# Charger.net
KiCad netlist of a schematic drawn in EAGLE
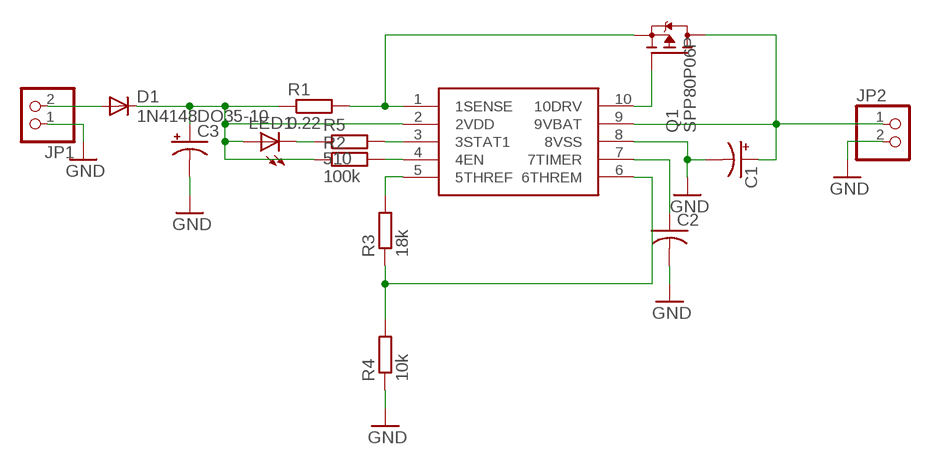
[diagram p0: schematic, sheet 1]

(export (version "E")
  (design (tool "Eeschema 10.0.6"))
  (components
    (comp (ref "C1")
      (value "CPOL-US153CLV-0505")
      (footprint "eagle-import:153CLV-0505")
      (libsource (lib "eagle-import") (part "CPOL-US153CLV-0505"))
    )
    (comp (ref "C2")
      (value "C-USC0805")
      (footprint "eagle-import:C0805")
      (libsource (lib "eagle-import") (part "C-USC0805"))
    )
    (comp (ref "C3")
      (value "CPOL-US153CLV-0505")
      (footprint "eagle-import:153CLV-0505")
      (libsource (lib "eagle-import") (part "CPOL-US153CLV-0505"))
    )
    (comp (ref "D1")
      (value "1N4148DO35-10")
      (footprint "eagle-import:DO35-10")
      (libsource (lib "eagle-import") (part "1N4148DO35-10"))
    )
    (comp (ref "JP1")
      (value "PINHD-1X2")
      (footprint "eagle-import:1X02")
      (libsource (lib "eagle-import") (part "PINHD-1X2"))
    )
    (comp (ref "JP2")
      (value "PINHD-1X2")
      (footprint "eagle-import:1X02")
      (libsource (lib "eagle-import") (part "PINHD-1X2"))
    )
    (comp (ref "LED1")
      (value "LEDCHIPLED_1206")
      (footprint "eagle-import:CHIPLED_1206")
      (libsource (lib "eagle-import") (part "LEDCHIPLED_1206"))
    )
    (comp (ref "Q1")
      (value "SPP80P06P")
      (footprint "eagle-import:TO220")
      (libsource (lib "eagle-import") (part "SPP80P06P"))
    )
    (comp (ref "R1")
      (value "0.22")
      (footprint "eagle-import:R0805")
      (libsource (lib "eagle-import") (part "R-EU_R0805"))
    )
    (comp (ref "R2")
      (value "100k")
      (footprint "eagle-import:R0805")
      (libsource (lib "eagle-import") (part "R-EU_R0805"))
    )
    (comp (ref "R3")
      (value "18k")
      (footprint "eagle-import:R0805")
      (libsource (lib "eagle-import") (part "R-EU_R0805"))
    )
    (comp (ref "R4")
      (value "10k")
      (footprint "eagle-import:R0805")
      (libsource (lib "eagle-import") (part "R-EU_R0805"))
    )
    (comp (ref "R5")
      (value "510")
      (footprint "eagle-import:R0805")
      (libsource (lib "eagle-import") (part "R-EU_R0805"))
    )
    (comp (ref "U$1")
      (value "MCP73841")
      (footprint "eagle-import:MSOP10")
      (libsource (lib "eagle-import") (part "MCP73841"))
    )
  )
  (nets
    (net (code "1") (name "GND") (class "Default")
      (node (ref "C1") (pin "-") (pinfunction "-_-") (pintype "passive"))
      (node (ref "C2") (pin "2") (pinfunction "2_2") (pintype "passive"))
      (node (ref "C3") (pin "-") (pinfunction "-_-") (pintype "passive"))
      (node (ref "JP1") (pin "1") (pinfunction "1_1") (pintype "passive"))
      (node (ref "JP2") (pin "2") (pinfunction "2_2") (pintype "passive"))
      (node (ref "R4") (pin "1") (pinfunction "1_1") (pintype "passive"))
      (node (ref "U$1") (pin "8") (pinfunction "8VSS_8") (pintype "bidirectional"))
    )
    (net (code "2") (name "Net-(D1-PadA)") (class "Default")
      (node (ref "D1") (pin "A") (pinfunction "A_A") (pintype "passive"))
      (node (ref "JP1") (pin "2") (pinfunction "2_2") (pintype "passive"))
    )
    (net (code "3") (name "Net-(LED1-PadC)") (class "Default")
      (node (ref "LED1") (pin "C") (pinfunction "C_C") (pintype "passive"))
      (node (ref "R5") (pin "1") (pinfunction "1_1") (pintype "passive"))
    )
    (net (code "4") (name "Net-(Q1-D)") (class "Default")
      (node (ref "C1") (pin "+") (pinfunction "+_+") (pintype "passive"))
      (node (ref "JP2") (pin "1") (pinfunction "1_1") (pintype "passive"))
      (node (ref "Q1") (pin "2") (pinfunction "D_2") (pintype "passive"))
      (node (ref "U$1") (pin "9") (pinfunction "9VBAT_9") (pintype "bidirectional"))
    )
    (net (code "5") (name "Net-(Q1-G)") (class "Default")
      (node (ref "Q1") (pin "1") (pinfunction "G_1") (pintype "passive"))
      (node (ref "U$1") (pin "10") (pinfunction "10DRV_10") (pintype "bidirectional"))
    )
    (net (code "6") (name "Net-(Q1-S)") (class "Default")
      (node (ref "Q1") (pin "3") (pinfunction "S_3") (pintype "passive"))
      (node (ref "R1") (pin "2") (pinfunction "2_2") (pintype "passive"))
      (node (ref "U$1") (pin "1") (pinfunction "1SENSE_1") (pintype "bidirectional"))
    )
    (net (code "7") (name "Net-(U$1-2VDD)") (class "Default")
      (node (ref "C3") (pin "+") (pinfunction "+_+") (pintype "passive"))
      (node (ref "D1") (pin "C") (pinfunction "C_C") (pintype "passive"))
      (node (ref "LED1") (pin "A") (pinfunction "A_A") (pintype "passive"))
      (node (ref "R1") (pin "1") (pinfunction "1_1") (pintype "passive"))
      (node (ref "R2") (pin "1") (pinfunction "1_1") (pintype "passive"))
      (node (ref "U$1") (pin "2") (pinfunction "2VDD_2") (pintype "bidirectional"))
    )
    (net (code "8") (name "Net-(U$1-3STAT1)") (class "Default")
      (node (ref "R5") (pin "2") (pinfunction "2_2") (pintype "passive"))
      (node (ref "U$1") (pin "3") (pinfunction "3STAT1_3") (pintype "bidirectional"))
    )
    (net (code "9") (name "Net-(U$1-4EN)") (class "Default")
      (node (ref "R2") (pin "2") (pinfunction "2_2") (pintype "passive"))
      (node (ref "U$1") (pin "4") (pinfunction "4EN_4") (pintype "bidirectional"))
    )
    (net (code "10") (name "Net-(U$1-5THREF)") (class "Default")
      (node (ref "R3") (pin "2") (pinfunction "2_2") (pintype "passive"))
      (node (ref "U$1") (pin "5") (pinfunction "5THREF_5") (pintype "bidirectional"))
    )
    (net (code "11") (name "Net-(U$1-6THREM)") (class "Default")
      (node (ref "R3") (pin "1") (pinfunction "1_1") (pintype "passive"))
      (node (ref "R4") (pin "2") (pinfunction "2_2") (pintype "passive"))
      (node (ref "U$1") (pin "6") (pinfunction "6THREM_6") (pintype "bidirectional"))
    )
    (net (code "12") (name "Net-(U$1-7TIMER)") (class "Default")
      (node (ref "C2") (pin "1") (pinfunction "1_1") (pintype "passive"))
      (node (ref "U$1") (pin "7") (pinfunction "7TIMER_7") (pintype "bidirectional"))
    )
  )
)
